# sensor_node3.net
KiCad netlist of a schematic drawn in EAGLE
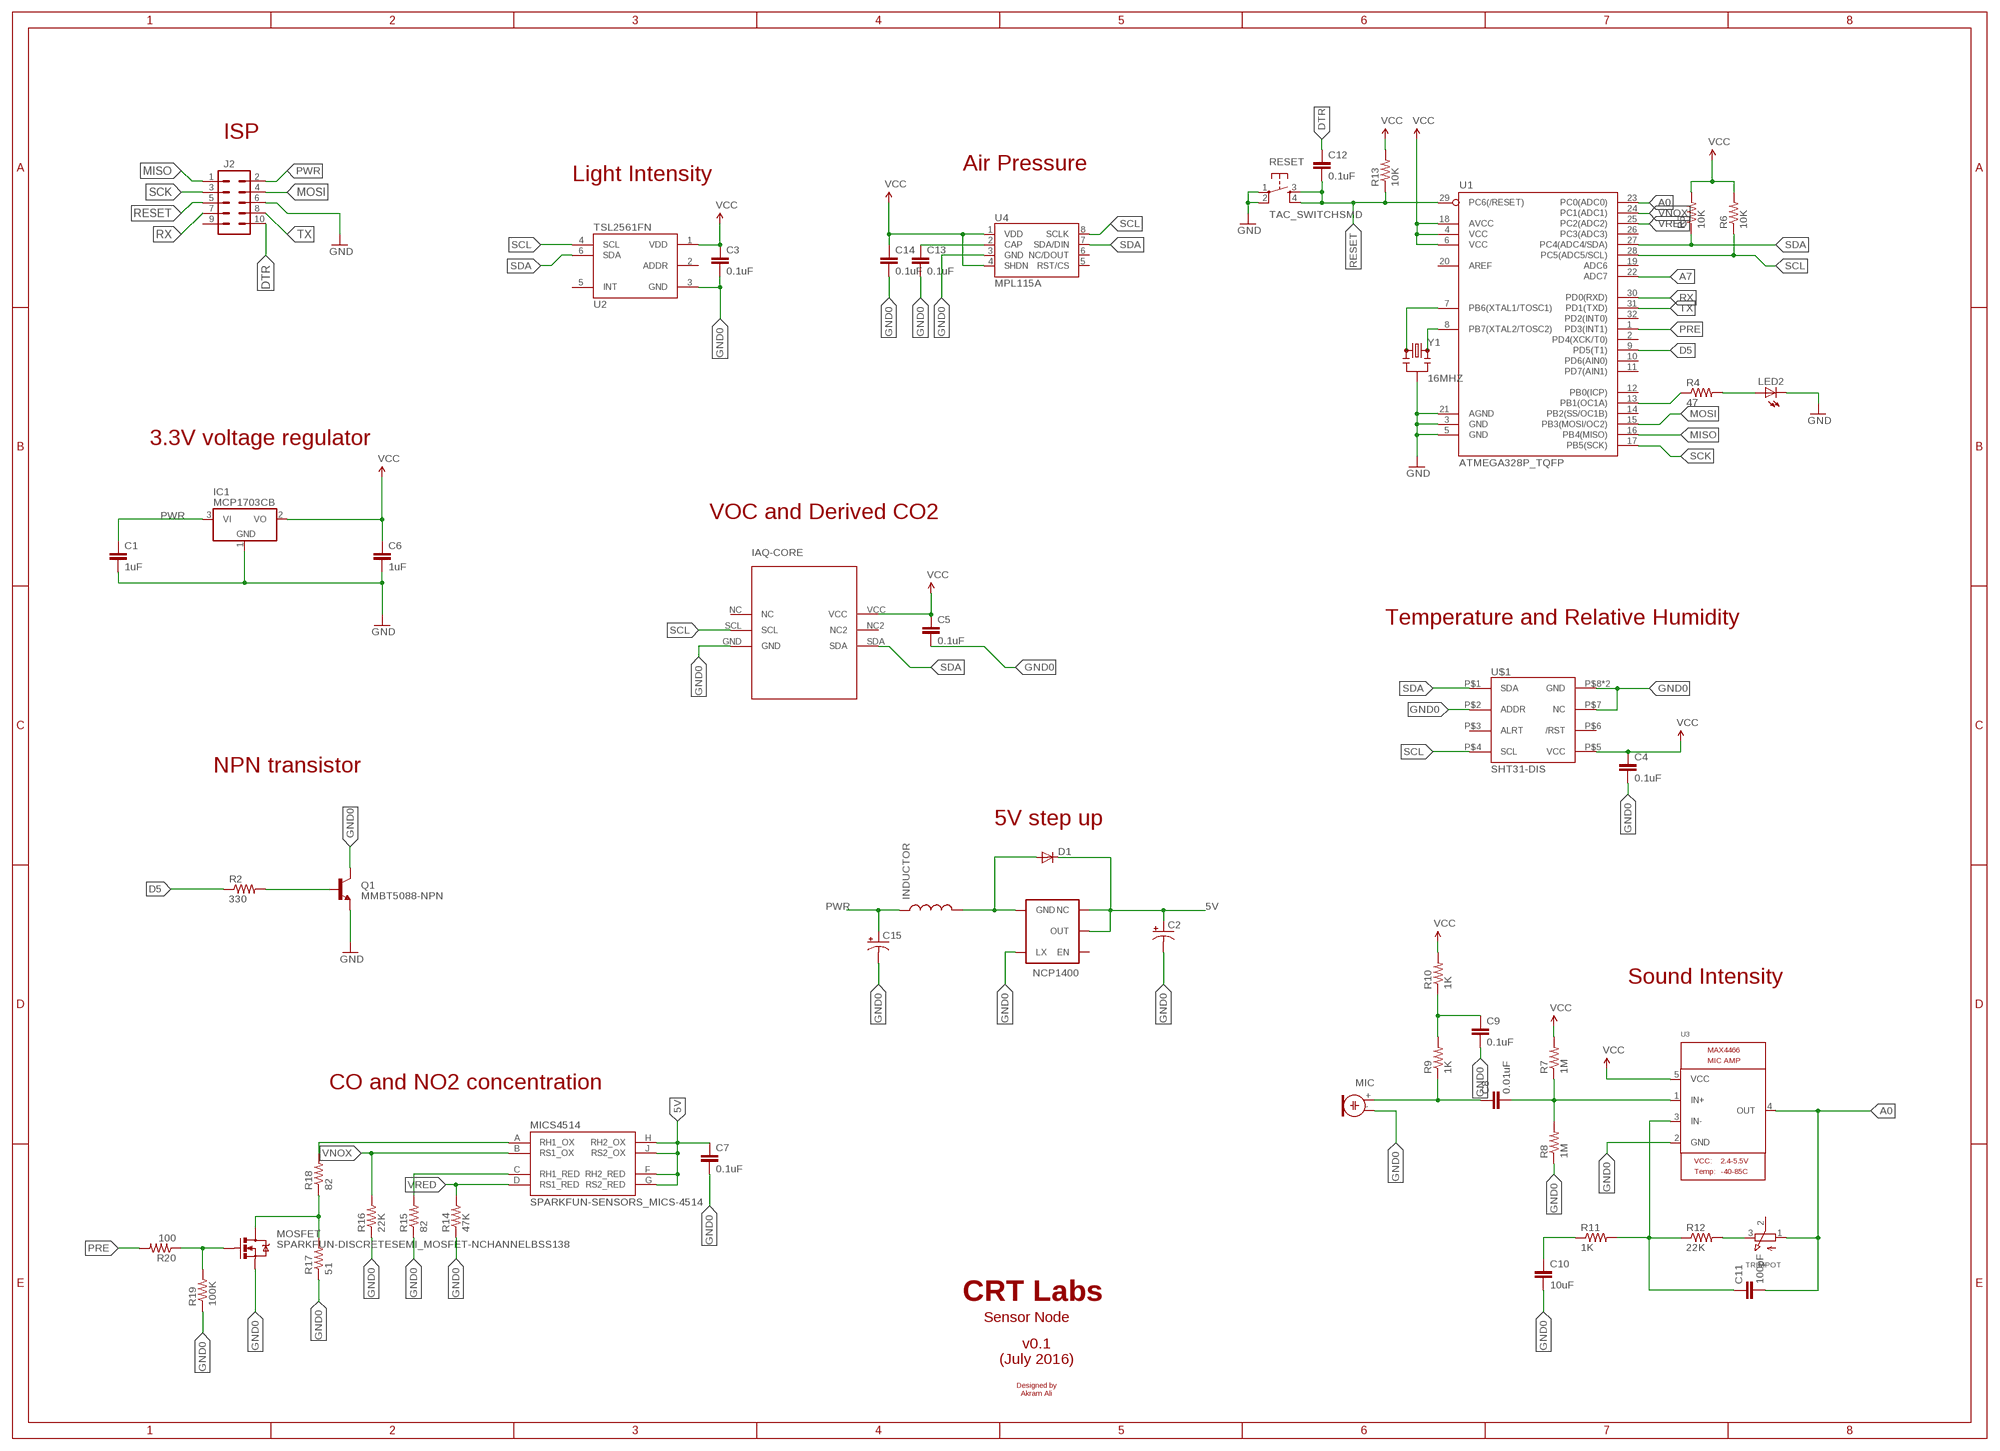
[diagram p0: schematic, sheet 1]

(export (version "E")
  (design (tool "Eeschema 10.0.6"))
  (components
    (comp (ref "C1")
      (value "1uF")
      (footprint "eagle-import:0805")
      (libsource (lib "eagle-import") (part "CAP0805"))
    )
    (comp (ref "C2")
      (value "CAP_POL3528")
      (footprint "eagle-import:EIA3528")
      (libsource (lib "eagle-import") (part "CAP_POL3528"))
    )
    (comp (ref "C3")
      (value "0.1uF")
      (footprint "eagle-import:0805")
      (libsource (lib "eagle-import") (part "SparkFun-Passives_CAP0805"))
    )
    (comp (ref "C4")
      (value "0.1uF")
      (footprint "eagle-import:0805")
      (libsource (lib "eagle-import") (part "SparkFun-Passives_CAP0805"))
    )
    (comp (ref "C5")
      (value "0.1uF")
      (footprint "eagle-import:0805")
      (libsource (lib "eagle-import") (part "SparkFun-Passives_CAP0805"))
    )
    (comp (ref "C6")
      (value "1uF")
      (footprint "eagle-import:0805")
      (libsource (lib "eagle-import") (part "CAP0805"))
    )
    (comp (ref "C7")
      (value "0.1uF")
      (footprint "eagle-import:0805")
      (libsource (lib "eagle-import") (part "SparkFun-Passives_CAP0805"))
    )
    (comp (ref "C8")
      (value "0.01uF")
      (footprint "eagle-import:0805")
      (libsource (lib "eagle-import") (part "SparkFun-Passives_CAP0805"))
    )
    (comp (ref "C9")
      (value "0.1uF")
      (footprint "eagle-import:0805")
      (libsource (lib "eagle-import") (part "SparkFun-Passives_CAP0805"))
    )
    (comp (ref "C10")
      (value "10uF")
      (footprint "eagle-import:0805")
      (libsource (lib "eagle-import") (part "SparkFun-Passives_CAP0805"))
    )
    (comp (ref "C11")
      (value "100pF")
      (footprint "eagle-import:0805")
      (libsource (lib "eagle-import") (part "SparkFun-Passives_CAP0805"))
    )
    (comp (ref "C12")
      (value "0.1uF")
      (footprint "eagle-import:0805")
      (libsource (lib "eagle-import") (part "SparkFun-Passives_CAP0805"))
    )
    (comp (ref "C13")
      (value "0.1uF")
      (footprint "eagle-import:0805")
      (libsource (lib "eagle-import") (part "SparkFun-Passives_CAP0805"))
    )
    (comp (ref "C14")
      (value "0.1uF")
      (footprint "eagle-import:0805")
      (libsource (lib "eagle-import") (part "SparkFun-Passives_CAP0805"))
    )
    (comp (ref "C15")
      (value "CAP_POL1206")
      (footprint "eagle-import:EIA3216")
      (libsource (lib "eagle-import") (part "CAP_POL1206"))
    )
    (comp (ref "D1")
      (value "DIODESMA")
      (footprint "eagle-import:SMA-DIODE")
      (libsource (lib "eagle-import") (part "DIODESMA"))
    )
    (comp (ref "IAQ-CORE")
      (value "IAQ-CORE")
      (footprint "eagle-import:IAQ-CORE")
      (fields (field (name "MPN") "IAQ CORE"))
      (libsource (lib "eagle-import") (part "IAQ-CORE"))
    )
    (comp (ref "IC1")
      (value "MCP1703CB")
      (footprint "eagle-import:SOT23")
      (fields (field (name "MPN") "MCP1703T-2502E/CB"))
      (libsource (lib "eagle-import") (part "MCP1703CB"))
    )
    (comp (ref "INDUCTOR")
      (value "INDUCTORCR54")
      (footprint "eagle-import:CR54")
      (libsource (lib "eagle-import") (part "INDUCTORCR54"))
    )
    (comp (ref "J2")
      (value "M05X2PTH")
      (footprint "eagle-import:AVR_ICSP")
      (libsource (lib "eagle-import") (part "M05X2PTH"))
    )
    (comp (ref "LED2")
      (value "LEDCHIPLED_0805")
      (footprint "eagle-import:CHIPLED_0805")
      (libsource (lib "eagle-import") (part "LEDCHIPLED_0805"))
    )
    (comp (ref "MIC")
      (value "ELECTRET")
      (footprint "eagle-import:ELECTRET_9.7")
      (libsource (lib "eagle-import") (part "ELECTRET"))
    )
    (comp (ref "MICS4514")
      (value "SPARKFUN-SENSORS_MICS-4514")
      (footprint "eagle-import:SPARKFUN-SENSORS_MICS_10-SMD")
      (libsource (lib "eagle-import") (part "SPARKFUN-SENSORS_MICS-4514"))
    )
    (comp (ref "MOSFET")
      (value "SPARKFUN-DISCRETESEMI_MOSFET-NCHANNELBSS138")
      (footprint "eagle-import:SPARKFUN-DISCRETESEMI_SOT23-3")
      (libsource (lib "eagle-import") (part "SPARKFUN-DISCRETESEMI_MOSFET-NCHANNELBSS138"))
    )
    (comp (ref "NCP1400")
      (value "V_REG_NCP1400SOT23-5")
      (footprint "eagle-import:SOT23-5")
      (libsource (lib "eagle-import") (part "V_REG_NCP1400SOT23-5"))
    )
    (comp (ref "Q1")
      (value "MMBT5088-NPN")
      (footprint "eagle-import:SOT23-3")
      (libsource (lib "eagle-import") (part "TRANSISTOR_NPNMMBT5088"))
    )
    (comp (ref "R2")
      (value "330")
      (footprint "eagle-import:0805")
      (libsource (lib "eagle-import") (part "RESISTOR0805-RES"))
    )
    (comp (ref "R4")
      (value "47")
      (footprint "eagle-import:0805")
      (libsource (lib "eagle-import") (part "SparkFun-Resistors_RESISTOR0805-RES"))
    )
    (comp (ref "R5")
      (value "10K")
      (footprint "eagle-import:0805")
      (libsource (lib "eagle-import") (part "SparkFun-Resistors_RESISTOR0805-RES"))
    )
    (comp (ref "R6")
      (value "10K")
      (footprint "eagle-import:0805")
      (libsource (lib "eagle-import") (part "SparkFun-Resistors_RESISTOR0805-RES"))
    )
    (comp (ref "R7")
      (value "1M")
      (footprint "eagle-import:0805")
      (libsource (lib "eagle-import") (part "RESISTOR0805-RES"))
    )
    (comp (ref "R8")
      (value "1M")
      (footprint "eagle-import:0805")
      (libsource (lib "eagle-import") (part "RESISTOR0805-RES"))
    )
    (comp (ref "R9")
      (value "1K")
      (footprint "eagle-import:0805")
      (libsource (lib "eagle-import") (part "RESISTOR0805-RES"))
    )
    (comp (ref "R10")
      (value "1K")
      (footprint "eagle-import:0805")
      (libsource (lib "eagle-import") (part "RESISTOR0805-RES"))
    )
    (comp (ref "R11")
      (value "1K")
      (footprint "eagle-import:0805")
      (libsource (lib "eagle-import") (part "RESISTOR0805-RES"))
    )
    (comp (ref "R12")
      (value "22K")
      (footprint "eagle-import:0805")
      (libsource (lib "eagle-import") (part "RESISTOR0805-RES"))
    )
    (comp (ref "R13")
      (value "10K")
      (footprint "eagle-import:0805")
      (libsource (lib "eagle-import") (part "RESISTOR0805-RES"))
    )
    (comp (ref "R14")
      (value "47K")
      (footprint "eagle-import:0805")
      (libsource (lib "eagle-import") (part "RESISTOR0805-RES"))
    )
    (comp (ref "R15")
      (value "82")
      (footprint "eagle-import:0805")
      (libsource (lib "eagle-import") (part "RESISTOR0805-RES"))
    )
    (comp (ref "R16")
      (value "22K")
      (footprint "eagle-import:0805")
      (libsource (lib "eagle-import") (part "RESISTOR0805-RES"))
    )
    (comp (ref "R17")
      (value "51")
      (footprint "eagle-import:0805")
      (libsource (lib "eagle-import") (part "RESISTOR0805-RES"))
    )
    (comp (ref "R18")
      (value "82")
      (footprint "eagle-import:0805")
      (libsource (lib "eagle-import") (part "RESISTOR0805-RES"))
    )
    (comp (ref "R19")
      (value "100K")
      (footprint "eagle-import:0805")
      (libsource (lib "eagle-import") (part "RESISTOR0805-RES"))
    )
    (comp (ref "R20")
      (value "100")
      (footprint "eagle-import:0805")
      (libsource (lib "eagle-import") (part "RESISTOR0805-RES"))
    )
    (comp (ref "RESET")
      (value "TAC_SWITCHSMD")
      (footprint "eagle-import:TACTILE-SWITCH-SMD")
      (libsource (lib "eagle-import") (part "TAC_SWITCHSMD"))
    )
    (comp (ref "TRIMPOT")
      (value "TRIMPOTTC33X-2")
      (footprint "eagle-import:TRIMPOT_BOURNS_TC33X-2")
      (libsource (lib "eagle-import") (part "TRIMPOTTC33X-2"))
    )
    (comp (ref "U$1")
      (value "SHT31-DIS")
      (footprint "eagle-import:SHT3X")
      (fields (field (name "MPN") "SHT31-DIS-B"))
      (libsource (lib "eagle-import") (part "SHT31-DIS"))
    )
    (comp (ref "U1")
      (value "ATMEGA328P_TQFP")
      (footprint "eagle-import:TQFP32-08")
      (fields (field (name "MPN") "ATMEGA328PB-AU"))
      (libsource (lib "eagle-import") (part "ATMEGA328P_TQFP"))
    )
    (comp (ref "U2")
      (value "TSL2561FN")
      (footprint "eagle-import:FN-6")
      (fields (field (name "MANF") "AMS-TAOS-USA-Inc."))
      (libsource (lib "eagle-import") (part "TSL2561FN"))
    )
    (comp (ref "U3")
      (value "MAX4466\"\"")
      (footprint "eagle-import:SC70-5")
      (fields (field (name "MPN") "MAX4466EXK+T"))
      (libsource (lib "eagle-import") (part "MAX4466{dblquote}{dblquote}"))
    )
    (comp (ref "U4")
      (value "MPL115A")
      (footprint "eagle-import:LGA8")
      (libsource (lib "eagle-import") (part "MPL115A"))
    )
    (comp (ref "Y1")
      (value "16MHZ")
      (footprint "eagle-import:RESONATOR-SMD")
      (libsource (lib "eagle-import") (part "RESONATOR16MHZ"))
    )
  )
  (nets
    (net (code "1") (name "5V") (class "Default")
      (node (ref "C2") (pin "A") (pinfunction "+_A") (pintype "passive"))
      (node (ref "C7") (pin "1") (pinfunction "1_1") (pintype "passive"))
      (node (ref "D1") (pin "C") (pinfunction "C_C") (pintype "passive"))
      (node (ref "MICS4514") (pin "F") (pinfunction "RH2_RED_F") (pintype "bidirectional"))
      (node (ref "MICS4514") (pin "G") (pinfunction "RS2_RED_G") (pintype "bidirectional"))
      (node (ref "MICS4514") (pin "H") (pinfunction "RH2_OX_H") (pintype "bidirectional"))
      (node (ref "MICS4514") (pin "J") (pinfunction "RS2_OX_J") (pintype "bidirectional"))
      (node (ref "NCP1400") (pin "2") (pinfunction "OUT_2") (pintype "passive"))
      (node (ref "NCP1400") (pin "3") (pinfunction "NC_3") (pintype "input"))
    )
    (net (code "2") (name "A0") (class "Default")
      (node (ref "C11") (pin "2") (pinfunction "2_2") (pintype "passive"))
      (node (ref "TRIMPOT") (pin "1") (pinfunction "A_1") (pintype "passive"))
      (node (ref "U1") (pin "23") (pinfunction "PC0(ADC0)_23") (pintype "bidirectional"))
      (node (ref "U3") (pin "4") (pinfunction "OUT_4") (pintype "bidirectional"))
    )
    (net (code "3") (name "A7") (class "Default")
      (node (ref "U1") (pin "22") (pinfunction "ADC7_22") (pintype "bidirectional"))
    )
    (net (code "4") (name "D5") (class "Default")
      (node (ref "R2") (pin "1") (pinfunction "1_1") (pintype "passive"))
      (node (ref "U1") (pin "9") (pinfunction "PD5(T1)_9") (pintype "bidirectional"))
    )
    (net (code "5") (name "DTR") (class "Default")
      (node (ref "C12") (pin "1") (pinfunction "1_1") (pintype "passive"))
      (node (ref "J2") (pin "10") (pinfunction "10_10") (pintype "passive"))
    )
    (net (code "6") (name "GND") (class "Default")
      (node (ref "C1") (pin "2") (pinfunction "2_2") (pintype "passive"))
      (node (ref "C6") (pin "2") (pinfunction "2_2") (pintype "passive"))
      (node (ref "IC1") (pin "1") (pinfunction "GND_1") (pintype "passive"))
      (node (ref "J2") (pin "6") (pinfunction "6_6") (pintype "passive"))
      (node (ref "LED2") (pin "C") (pinfunction "C_C") (pintype "passive"))
      (node (ref "Q1") (pin "2") (pinfunction "E_2") (pintype "passive"))
      (node (ref "RESET") (pin "1") (pinfunction "1_1") (pintype "passive"))
      (node (ref "RESET") (pin "2") (pinfunction "2_2") (pintype "passive"))
      (node (ref "U1") (pin "21") (pinfunction "AGND_21") (pintype "bidirectional"))
      (node (ref "U1") (pin "3") (pinfunction "GND_3") (pintype "bidirectional"))
      (node (ref "U1") (pin "5") (pinfunction "GND_5") (pintype "bidirectional"))
      (node (ref "Y1") (pin "2") (pinfunction "2_2") (pintype "passive"))
    )
    (net (code "7") (name "GND0") (class "Default")
      (node (ref "C10") (pin "2") (pinfunction "2_2") (pintype "passive"))
      (node (ref "C13") (pin "2") (pinfunction "2_2") (pintype "passive"))
      (node (ref "C14") (pin "2") (pinfunction "2_2") (pintype "passive"))
      (node (ref "C15") (pin "C") (pinfunction "-_C") (pintype "passive"))
      (node (ref "C2") (pin "C") (pinfunction "-_C") (pintype "passive"))
      (node (ref "C3") (pin "2") (pinfunction "2_2") (pintype "passive"))
      (node (ref "C4") (pin "2") (pinfunction "2_2") (pintype "passive"))
      (node (ref "C5") (pin "2") (pinfunction "2_2") (pintype "passive"))
      (node (ref "C7") (pin "2") (pinfunction "2_2") (pintype "passive"))
      (node (ref "C9") (pin "2") (pinfunction "2_2") (pintype "passive"))
      (node (ref "IAQ-CORE") (pin "GND") (pinfunction "GND_GND") (pintype "bidirectional"))
      (node (ref "MIC") (pin "-") (pinfunction "1_-") (pintype "passive"))
      (node (ref "MOSFET") (pin "2") (pinfunction "S_2") (pintype "passive"))
      (node (ref "NCP1400") (pin "5") (pinfunction "LX_5") (pintype "input"))
      (node (ref "Q1") (pin "3") (pinfunction "C_3") (pintype "passive"))
      (node (ref "R14") (pin "1") (pinfunction "1_1") (pintype "passive"))
      (node (ref "R15") (pin "1") (pinfunction "1_1") (pintype "passive"))
      (node (ref "R16") (pin "1") (pinfunction "1_1") (pintype "passive"))
      (node (ref "R17") (pin "1") (pinfunction "1_1") (pintype "passive"))
      (node (ref "R19") (pin "1") (pinfunction "1_1") (pintype "passive"))
      (node (ref "R8") (pin "1") (pinfunction "1_1") (pintype "passive"))
      (node (ref "U$1") (pin "P$2") (pinfunction "ADDR_P$2") (pintype "bidirectional"))
      (node (ref "U$1") (pin "P$7") (pinfunction "NC_P$7") (pintype "bidirectional"))
      (node (ref "U$1") (pin "P$8") (pinfunction "GND_P$8") (pintype "bidirectional"))
      (node (ref "U$1") (pin "PAD") (pinfunction "GND_PAD") (pintype "bidirectional"))
      (node (ref "U2") (pin "3") (pinfunction "GND_3") (pintype "power_in"))
      (node (ref "U3") (pin "2") (pinfunction "GND_2") (pintype "bidirectional"))
      (node (ref "U4") (pin "3") (pinfunction "GND_3") (pintype "bidirectional"))
    )
    (net (code "8") (name "MISO") (class "Default")
      (node (ref "J2") (pin "1") (pinfunction "1_1") (pintype "passive"))
      (node (ref "U1") (pin "16") (pinfunction "PB4(MISO)_16") (pintype "bidirectional"))
    )
    (net (code "9") (name "MOSI") (class "Default")
      (node (ref "J2") (pin "4") (pinfunction "4_4") (pintype "passive"))
      (node (ref "U1") (pin "15") (pinfunction "PB3(MOSI/OC2)_15") (pintype "bidirectional"))
    )
    (net (code "10") (name "Net-(C9-Pad1)") (class "Default")
      (node (ref "C9") (pin "1") (pinfunction "1_1") (pintype "passive"))
      (node (ref "R10") (pin "1") (pinfunction "1_1") (pintype "passive"))
      (node (ref "R9") (pin "2") (pinfunction "2_2") (pintype "passive"))
    )
    (net (code "11") (name "Net-(C10-Pad1)") (class "Default")
      (node (ref "C10") (pin "1") (pinfunction "1_1") (pintype "passive"))
      (node (ref "R11") (pin "1") (pinfunction "1_1") (pintype "passive"))
    )
    (net (code "12") (name "Net-(INDUCTOR-2)") (class "Default")
      (node (ref "D1") (pin "A") (pinfunction "A_A") (pintype "passive"))
      (node (ref "INDUCTOR") (pin "P$2") (pinfunction "2_P$2") (pintype "passive"))
      (node (ref "NCP1400") (pin "4") (pinfunction "GND_4") (pintype "input"))
    )
    (net (code "13") (name "Net-(LED2-PadA)") (class "Default")
      (node (ref "LED2") (pin "A") (pinfunction "A_A") (pintype "passive"))
      (node (ref "R4") (pin "2") (pinfunction "2_2") (pintype "passive"))
    )
    (net (code "14") (name "Net-(MIC-2)") (class "Default")
      (node (ref "C8") (pin "1") (pinfunction "1_1") (pintype "passive"))
      (node (ref "MIC") (pin "+") (pinfunction "2_+") (pintype "passive"))
      (node (ref "R9") (pin "1") (pinfunction "1_1") (pintype "passive"))
    )
    (net (code "15") (name "Net-(MICS4514-RH1_OX)") (class "Default")
      (node (ref "MICS4514") (pin "A") (pinfunction "RH1_OX_A") (pintype "bidirectional"))
      (node (ref "R18") (pin "2") (pinfunction "2_2") (pintype "passive"))
    )
    (net (code "16") (name "Net-(MICS4514-RH1_RED)") (class "Default")
      (node (ref "MICS4514") (pin "C") (pinfunction "RH1_RED_C") (pintype "bidirectional"))
      (node (ref "R15") (pin "2") (pinfunction "2_2") (pintype "passive"))
    )
    (net (code "17") (name "Net-(MOSFET-D)") (class "Default")
      (node (ref "MOSFET") (pin "3") (pinfunction "D_3") (pintype "passive"))
      (node (ref "R17") (pin "2") (pinfunction "2_2") (pintype "passive"))
      (node (ref "R18") (pin "1") (pinfunction "1_1") (pintype "passive"))
    )
    (net (code "18") (name "Net-(MOSFET-G)") (class "Default")
      (node (ref "MOSFET") (pin "1") (pinfunction "G_1") (pintype "passive"))
      (node (ref "R19") (pin "2") (pinfunction "2_2") (pintype "passive"))
      (node (ref "R20") (pin "1") (pinfunction "1_1") (pintype "passive"))
    )
    (net (code "19") (name "Net-(Q1-B)") (class "Default")
      (node (ref "Q1") (pin "1") (pinfunction "B_1") (pintype "passive"))
      (node (ref "R2") (pin "2") (pinfunction "2_2") (pintype "passive"))
    )
    (net (code "20") (name "Net-(TRIMPOT-E)") (class "Default")
      (node (ref "R12") (pin "2") (pinfunction "2_2") (pintype "passive"))
      (node (ref "TRIMPOT") (pin "3") (pinfunction "E_3") (pintype "passive"))
    )
    (net (code "21") (name "Net-(U1-PB1(OC1A))") (class "Default")
      (node (ref "R4") (pin "1") (pinfunction "1_1") (pintype "passive"))
      (node (ref "U1") (pin "13") (pinfunction "PB1(OC1A)_13") (pintype "bidirectional"))
    )
    (net (code "22") (name "Net-(U1-PB6(XTAL1{slash}TOSC1))") (class "Default")
      (node (ref "U1") (pin "7") (pinfunction "PB6(XTAL1/TOSC1)_7") (pintype "bidirectional"))
      (node (ref "Y1") (pin "1") (pinfunction "1_1") (pintype "passive"))
    )
    (net (code "23") (name "Net-(U1-PB7(XTAL2{slash}TOSC2))") (class "Default")
      (node (ref "U1") (pin "8") (pinfunction "PB7(XTAL2/TOSC2)_8") (pintype "bidirectional"))
      (node (ref "Y1") (pin "3") (pinfunction "3_3") (pintype "passive"))
    )
    (net (code "24") (name "Net-(U3-IN+)") (class "Default")
      (node (ref "C8") (pin "2") (pinfunction "2_2") (pintype "passive"))
      (node (ref "R7") (pin "1") (pinfunction "1_1") (pintype "passive"))
      (node (ref "R8") (pin "2") (pinfunction "2_2") (pintype "passive"))
      (node (ref "U3") (pin "1") (pinfunction "IN+_1") (pintype "bidirectional"))
    )
    (net (code "25") (name "Net-(U3-IN-)") (class "Default")
      (node (ref "C11") (pin "1") (pinfunction "1_1") (pintype "passive"))
      (node (ref "R11") (pin "2") (pinfunction "2_2") (pintype "passive"))
      (node (ref "R12") (pin "1") (pinfunction "1_1") (pintype "passive"))
      (node (ref "U3") (pin "3") (pinfunction "IN-_3") (pintype "bidirectional"))
    )
    (net (code "26") (name "Net-(U4-CAP)") (class "Default")
      (node (ref "C13") (pin "1") (pinfunction "1_1") (pintype "passive"))
      (node (ref "U4") (pin "2") (pinfunction "CAP_2") (pintype "bidirectional"))
    )
    (net (code "27") (name "PRE") (class "Default")
      (node (ref "R20") (pin "2") (pinfunction "2_2") (pintype "passive"))
      (node (ref "U1") (pin "1") (pinfunction "PD3(INT1)_1") (pintype "bidirectional"))
    )
    (net (code "28") (name "PWR") (class "Default")
      (node (ref "C1") (pin "1") (pinfunction "1_1") (pintype "passive"))
      (node (ref "C15") (pin "A") (pinfunction "+_A") (pintype "passive"))
      (node (ref "IC1") (pin "3") (pinfunction "VI_3") (pintype "input"))
      (node (ref "INDUCTOR") (pin "P$1") (pinfunction "1_P$1") (pintype "passive"))
      (node (ref "J2") (pin "2") (pinfunction "2_2") (pintype "passive"))
    )
    (net (code "29") (name "RESET") (class "Default")
      (node (ref "C12") (pin "2") (pinfunction "2_2") (pintype "passive"))
      (node (ref "J2") (pin "5") (pinfunction "5_5") (pintype "passive"))
      (node (ref "R13") (pin "1") (pinfunction "1_1") (pintype "passive"))
      (node (ref "RESET") (pin "3") (pinfunction "3_3") (pintype "passive"))
      (node (ref "RESET") (pin "4") (pinfunction "4_4") (pintype "passive"))
      (node (ref "U1") (pin "29") (pinfunction "PC6(/RESET)_29") (pintype "bidirectional"))
    )
    (net (code "30") (name "RX") (class "Default")
      (node (ref "J2") (pin "7") (pinfunction "7_7") (pintype "passive"))
      (node (ref "U1") (pin "30") (pinfunction "PD0(RXD)_30") (pintype "bidirectional"))
    )
    (net (code "31") (name "SCK") (class "Default")
      (node (ref "J2") (pin "3") (pinfunction "3_3") (pintype "passive"))
      (node (ref "U1") (pin "17") (pinfunction "PB5(SCK)_17") (pintype "bidirectional"))
    )
    (net (code "32") (name "SCL") (class "Default")
      (node (ref "IAQ-CORE") (pin "SCL") (pinfunction "SCL_SCL") (pintype "bidirectional"))
      (node (ref "R6") (pin "1") (pinfunction "1_1") (pintype "passive"))
      (node (ref "U$1") (pin "P$4") (pinfunction "SCL_P$4") (pintype "bidirectional"))
      (node (ref "U1") (pin "28") (pinfunction "PC5(ADC5/SCL)_28") (pintype "bidirectional"))
      (node (ref "U2") (pin "4") (pinfunction "SCL_4") (pintype "input"))
      (node (ref "U4") (pin "8") (pinfunction "SCLK_8") (pintype "bidirectional"))
    )
    (net (code "33") (name "SDA") (class "Default")
      (node (ref "IAQ-CORE") (pin "SDA") (pinfunction "SDA_SDA") (pintype "bidirectional"))
      (node (ref "R5") (pin "1") (pinfunction "1_1") (pintype "passive"))
      (node (ref "U$1") (pin "P$1") (pinfunction "SDA_P$1") (pintype "bidirectional"))
      (node (ref "U1") (pin "27") (pinfunction "PC4(ADC4/SDA)_27") (pintype "bidirectional"))
      (node (ref "U2") (pin "6") (pinfunction "SDA_6") (pintype "bidirectional"))
      (node (ref "U4") (pin "7") (pinfunction "SDA/DIN_7") (pintype "bidirectional"))
    )
    (net (code "34") (name "TX") (class "Default")
      (node (ref "J2") (pin "8") (pinfunction "8_8") (pintype "passive"))
      (node (ref "U1") (pin "31") (pinfunction "PD1(TXD)_31") (pintype "bidirectional"))
    )
    (net (code "35") (name "VCC") (class "Default")
      (node (ref "C14") (pin "1") (pinfunction "1_1") (pintype "passive"))
      (node (ref "C3") (pin "1") (pinfunction "1_1") (pintype "passive"))
      (node (ref "C4") (pin "1") (pinfunction "1_1") (pintype "passive"))
      (node (ref "C5") (pin "1") (pinfunction "1_1") (pintype "passive"))
      (node (ref "C6") (pin "1") (pinfunction "1_1") (pintype "passive"))
      (node (ref "IAQ-CORE") (pin "VCC") (pinfunction "VCC_VCC") (pintype "bidirectional"))
      (node (ref "IC1") (pin "2") (pinfunction "VO_2") (pintype "passive"))
      (node (ref "R10") (pin "2") (pinfunction "2_2") (pintype "passive"))
      (node (ref "R13") (pin "2") (pinfunction "2_2") (pintype "passive"))
      (node (ref "R5") (pin "2") (pinfunction "2_2") (pintype "passive"))
      (node (ref "R6") (pin "2") (pinfunction "2_2") (pintype "passive"))
      (node (ref "R7") (pin "2") (pinfunction "2_2") (pintype "passive"))
      (node (ref "U$1") (pin "P$5") (pinfunction "VCC_P$5") (pintype "bidirectional"))
      (node (ref "U1") (pin "18") (pinfunction "AVCC_18") (pintype "bidirectional"))
      (node (ref "U1") (pin "4") (pinfunction "VCC_4") (pintype "bidirectional"))
      (node (ref "U1") (pin "6") (pinfunction "VCC_6") (pintype "bidirectional"))
      (node (ref "U2") (pin "1") (pinfunction "VDD_1") (pintype "power_in"))
      (node (ref "U3") (pin "5") (pinfunction "VCC_5") (pintype "bidirectional"))
      (node (ref "U4") (pin "1") (pinfunction "VDD_1") (pintype "bidirectional"))
      (node (ref "U4") (pin "4") (pinfunction "SHDN_4") (pintype "bidirectional"))
    )
    (net (code "36") (name "VNOX") (class "Default")
      (node (ref "MICS4514") (pin "B") (pinfunction "RS1_OX_B") (pintype "bidirectional"))
      (node (ref "R16") (pin "2") (pinfunction "2_2") (pintype "passive"))
      (node (ref "U1") (pin "24") (pinfunction "PC1(ADC1)_24") (pintype "bidirectional"))
    )
    (net (code "37") (name "VRED") (class "Default")
      (node (ref "MICS4514") (pin "D") (pinfunction "RS1_RED_D") (pintype "bidirectional"))
      (node (ref "R14") (pin "2") (pinfunction "2_2") (pintype "passive"))
      (node (ref "U1") (pin "25") (pinfunction "PC2(ADC2)_25") (pintype "bidirectional"))
    )
    (net (code "38") (name "unconnected-(IAQ-CORE-PadNC)") (class "Default")
      (node (ref "IAQ-CORE") (pin "NC") (pinfunction "NC_NC") (pintype "bidirectional"))
    )
    (net (code "39") (name "unconnected-(IAQ-CORE-PadNC2)") (class "Default")
      (node (ref "IAQ-CORE") (pin "NC2") (pinfunction "NC2_NC2") (pintype "bidirectional"))
    )
    (net (code "40") (name "unconnected-(J2-Pad9)") (class "Default")
      (node (ref "J2") (pin "9") (pinfunction "9_9") (pintype "passive"))
    )
    (net (code "41") (name "unconnected-(NCP1400-EN-Pad1)") (class "Default")
      (node (ref "NCP1400") (pin "1") (pinfunction "EN_1") (pintype "input"))
    )
    (net (code "42") (name "unconnected-(TRIMPOT-S-Pad2)") (class "Default")
      (node (ref "TRIMPOT") (pin "2") (pinfunction "S_2") (pintype "passive"))
    )
    (net (code "43") (name "unconnected-(U$1-ALRT-PadP$3)") (class "Default")
      (node (ref "U$1") (pin "P$3") (pinfunction "ALRT_P$3") (pintype "bidirectional"))
    )
    (net (code "44") (name "unconnected-(U$1-{slash}RST-PadP$6)") (class "Default")
      (node (ref "U$1") (pin "P$6") (pinfunction "/RST_P$6") (pintype "bidirectional"))
    )
    (net (code "45") (name "unconnected-(U1-ADC6-Pad19)") (class "Default")
      (node (ref "U1") (pin "19") (pinfunction "ADC6_19") (pintype "bidirectional"))
    )
    (net (code "46") (name "unconnected-(U1-AREF-Pad20)") (class "Default")
      (node (ref "U1") (pin "20") (pinfunction "AREF_20") (pintype "bidirectional"))
    )
    (net (code "47") (name "unconnected-(U1-PB0(ICP)-Pad12)") (class "Default")
      (node (ref "U1") (pin "12") (pinfunction "PB0(ICP)_12") (pintype "bidirectional"))
    )
    (net (code "48") (name "unconnected-(U1-PB2(SS{slash}OC1B)-Pad14)") (class "Default")
      (node (ref "U1") (pin "14") (pinfunction "PB2(SS/OC1B)_14") (pintype "bidirectional"))
    )
    (net (code "49") (name "unconnected-(U1-PC3(ADC3)-Pad26)") (class "Default")
      (node (ref "U1") (pin "26") (pinfunction "PC3(ADC3)_26") (pintype "bidirectional"))
    )
    (net (code "50") (name "unconnected-(U1-PD2(INT0)-Pad32)") (class "Default")
      (node (ref "U1") (pin "32") (pinfunction "PD2(INT0)_32") (pintype "bidirectional"))
    )
    (net (code "51") (name "unconnected-(U1-PD4(XCK{slash}T0)-Pad2)") (class "Default")
      (node (ref "U1") (pin "2") (pinfunction "PD4(XCK/T0)_2") (pintype "bidirectional"))
    )
    (net (code "52") (name "unconnected-(U1-PD6(AIN0)-Pad10)") (class "Default")
      (node (ref "U1") (pin "10") (pinfunction "PD6(AIN0)_10") (pintype "bidirectional"))
    )
    (net (code "53") (name "unconnected-(U1-PD7(AIN1)-Pad11)") (class "Default")
      (node (ref "U1") (pin "11") (pinfunction "PD7(AIN1)_11") (pintype "bidirectional"))
    )
    (net (code "54") (name "unconnected-(U2-ADDR-Pad2)") (class "Default")
      (node (ref "U2") (pin "2") (pinfunction "ADDR_2") (pintype "input"))
    )
    (net (code "55") (name "unconnected-(U2-INT-Pad5)") (class "Default")
      (node (ref "U2") (pin "5") (pinfunction "INT_5") (pintype "output"))
    )
    (net (code "56") (name "unconnected-(U4-NC{slash}DOUT-Pad6)") (class "Default")
      (node (ref "U4") (pin "6") (pinfunction "NC/DOUT_6") (pintype "bidirectional"))
    )
    (net (code "57") (name "unconnected-(U4-RST{slash}CS-Pad5)") (class "Default")
      (node (ref "U4") (pin "5") (pinfunction "RST/CS_5") (pintype "bidirectional"))
    )
  )
)
